# ui_ux6.net
KiCad netlist of a schematic drawn in Altium Designer
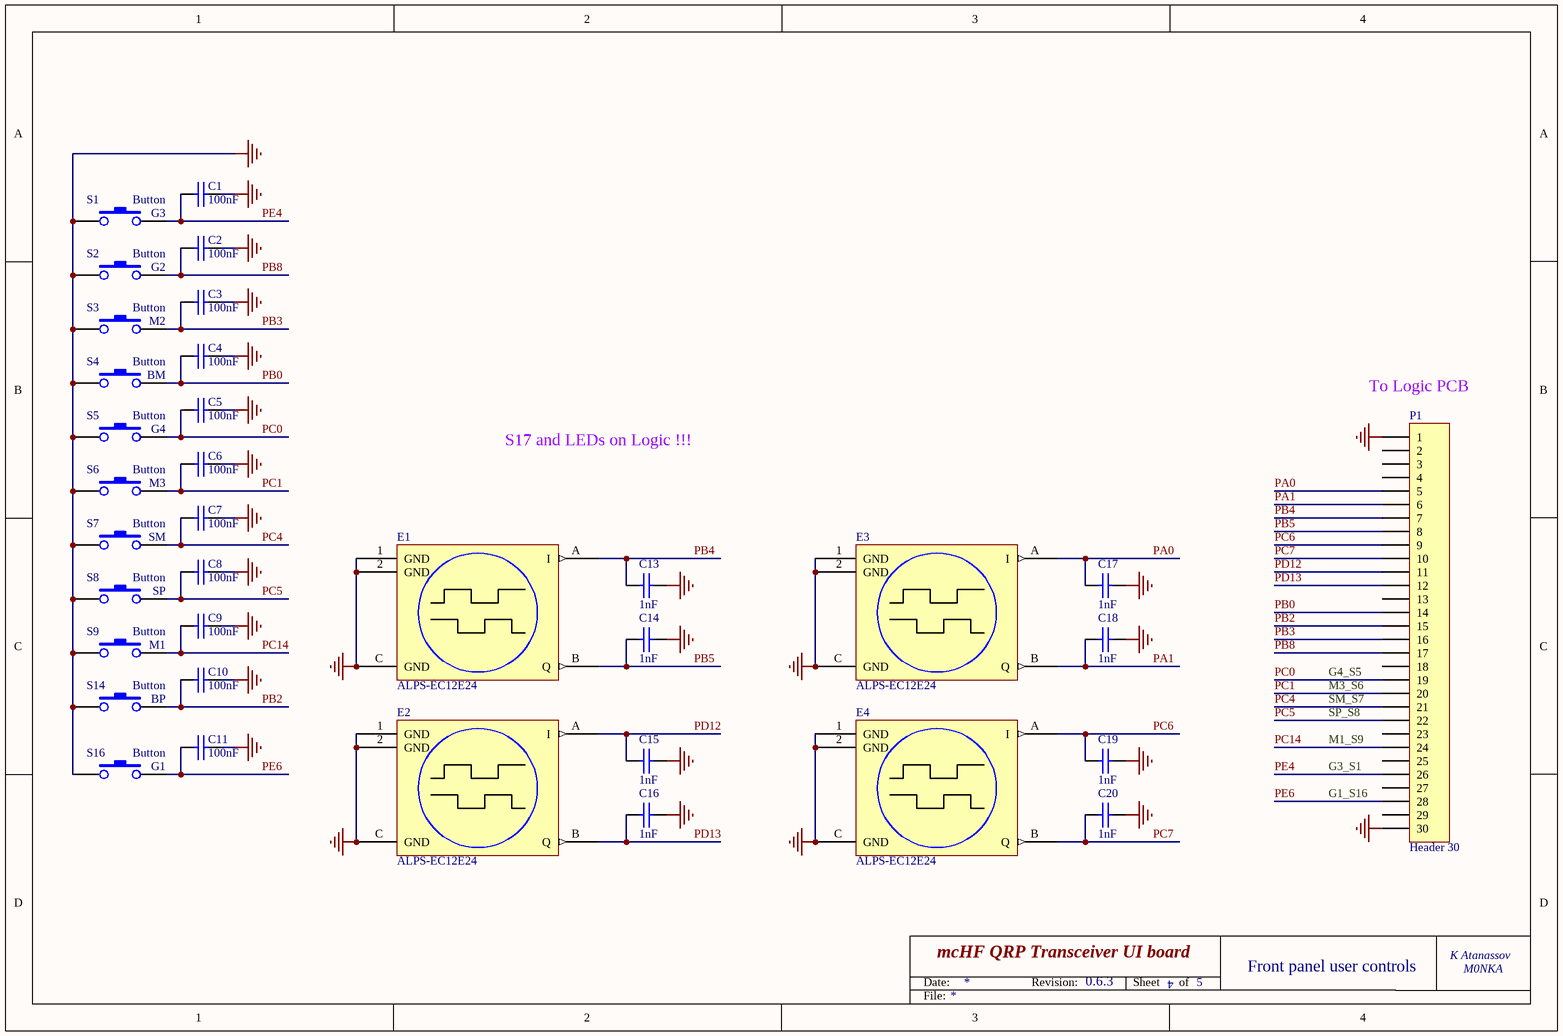
[diagram p0: ui_ux6.SchDoc]

(export (version "E")
  (design (tool "Eeschema 10.0.6"))
  (components
    (comp (ref "C1")
      (value "100nF")
      (footprint "0805-Pro")
      (description "Capacitor")
      (libsource (lib "mcHF_ui") (part "CAP"))
    )
    (comp (ref "C2")
      (value "100nF")
      (footprint "0805-Pro")
      (description "Capacitor")
      (libsource (lib "mcHF_ui") (part "CAP"))
    )
    (comp (ref "C3")
      (value "100nF")
      (footprint "0805-Pro")
      (description "Capacitor")
      (libsource (lib "mcHF_ui") (part "CAP"))
    )
    (comp (ref "C4")
      (value "100nF")
      (footprint "0805-Pro")
      (description "Capacitor")
      (libsource (lib "mcHF_ui") (part "CAP"))
    )
    (comp (ref "C5")
      (value "100nF")
      (footprint "0805-Pro")
      (description "Capacitor")
      (libsource (lib "mcHF_ui") (part "CAP"))
    )
    (comp (ref "C6")
      (value "100nF")
      (footprint "0805-Pro")
      (description "Capacitor")
      (libsource (lib "mcHF_ui") (part "CAP"))
    )
    (comp (ref "C7")
      (value "100nF")
      (footprint "0805-Pro")
      (description "Capacitor")
      (libsource (lib "mcHF_ui") (part "CAP"))
    )
    (comp (ref "C8")
      (value "100nF")
      (footprint "0805-Pro")
      (description "Capacitor")
      (libsource (lib "mcHF_ui") (part "CAP"))
    )
    (comp (ref "C9")
      (value "100nF")
      (footprint "0805-Pro")
      (description "Capacitor")
      (libsource (lib "mcHF_ui") (part "CAP"))
    )
    (comp (ref "C10")
      (value "100nF")
      (footprint "0805-Pro")
      (description "Capacitor")
      (libsource (lib "mcHF_ui") (part "CAP"))
    )
    (comp (ref "C11")
      (value "100nF")
      (footprint "0805-Pro")
      (description "Capacitor")
      (libsource (lib "mcHF_ui") (part "CAP"))
    )
    (comp (ref "C13")
      (value "1nF")
      (footprint "0805-Pro")
      (description "Capacitor")
      (libsource (lib "mcHF_ui") (part "CAP"))
    )
    (comp (ref "C14")
      (value "1nF")
      (footprint "0805-Pro")
      (description "Capacitor")
      (libsource (lib "mcHF_ui") (part "CAP"))
    )
    (comp (ref "C15")
      (value "1nF")
      (footprint "0805-Pro")
      (description "Capacitor")
      (libsource (lib "mcHF_ui") (part "CAP"))
    )
    (comp (ref "C16")
      (value "1nF")
      (footprint "0805-Pro")
      (description "Capacitor")
      (libsource (lib "mcHF_ui") (part "CAP"))
    )
    (comp (ref "C17")
      (value "1nF")
      (footprint "0805-Pro")
      (description "Capacitor")
      (libsource (lib "mcHF_ui") (part "CAP"))
    )
    (comp (ref "C18")
      (value "1nF")
      (footprint "0805-Pro")
      (description "Capacitor")
      (libsource (lib "mcHF_ui") (part "CAP"))
    )
    (comp (ref "C19")
      (value "1nF")
      (footprint "0805-Pro")
      (description "Capacitor")
      (libsource (lib "mcHF_ui") (part "CAP"))
    )
    (comp (ref "C20")
      (value "1nF")
      (footprint "0805-Pro")
      (description "Capacitor")
      (libsource (lib "mcHF_ui") (part "CAP"))
    )
    (comp (ref "E1")
      (value "ALPS-EC12E24")
      (footprint "Encoder")
      (description "ALPS Rotary Encoder")
      (libsource (lib "mcHF_ui") (part "Encoder"))
    )
    (comp (ref "E2")
      (value "ALPS-EC12E24")
      (footprint "Encoder")
      (description "ALPS Rotary Encoder")
      (libsource (lib "mcHF_ui") (part "Encoder"))
    )
    (comp (ref "E3")
      (value "ALPS-EC12E24")
      (footprint "Encoder")
      (description "ALPS Rotary Encoder")
      (libsource (lib "mcHF_ui") (part "Encoder"))
    )
    (comp (ref "E4")
      (value "ALPS-EC12E24")
      (footprint "Encoder")
      (description "ALPS Rotary Encoder")
      (libsource (lib "mcHF_ui") (part "Encoder"))
    )
    (comp (ref "P1")
      (value "Header 30")
      (footprint "HDR1X30")
      (description "Header, 30-Pin")
      (libsource (lib "mcHF_ui") (part "Header 30"))
    )
    (comp (ref "S1")
      (value "Button")
      (footprint "BUTTON_SMD2")
      (description "Push Button")
      (fields (field (name "SOFTWARE FUNCTION") "G3"))
      (libsource (lib "mcHF_ui") (part "SW-PB"))
    )
    (comp (ref "S2")
      (value "Button")
      (footprint "BUTTON_SMD2")
      (description "Push Button")
      (fields (field (name "SOFTWARE FUNCTION") "G2"))
      (libsource (lib "mcHF_ui") (part "SW-PB"))
    )
    (comp (ref "S3")
      (value "Button")
      (footprint "BUTTON_SMD2")
      (description "Push Button")
      (fields (field (name "SOFTWARE FUNCTION") "M2"))
      (libsource (lib "mcHF_ui") (part "SW-PB"))
    )
    (comp (ref "S4")
      (value "Button")
      (footprint "BUTTON_SMD2")
      (description "Push Button")
      (fields (field (name "SOFTWARE FUNCTION") "BM"))
      (libsource (lib "mcHF_ui") (part "SW-PB"))
    )
    (comp (ref "S5")
      (value "Button")
      (footprint "BUTTON_SMD2")
      (description "Push Button")
      (fields (field (name "SOFTWARE FUNCTION") "G4"))
      (libsource (lib "mcHF_ui") (part "SW-PB"))
    )
    (comp (ref "S6")
      (value "Button")
      (footprint "BUTTON_SMD2")
      (description "Push Button")
      (fields (field (name "SOFTWARE FUNCTION") "M3"))
      (libsource (lib "mcHF_ui") (part "SW-PB"))
    )
    (comp (ref "S7")
      (value "Button")
      (footprint "BUTTON_SMD2")
      (description "Push Button")
      (fields (field (name "SOFTWARE FUNCTION") "SM"))
      (libsource (lib "mcHF_ui") (part "SW-PB"))
    )
    (comp (ref "S8")
      (value "Button")
      (footprint "BUTTON_SMD2")
      (description "Push Button")
      (fields (field (name "SOFTWARE FUNCTION") "SP"))
      (libsource (lib "mcHF_ui") (part "SW-PB"))
    )
    (comp (ref "S9")
      (value "Button")
      (footprint "BUTTON_SMD2")
      (description "Push Button")
      (fields (field (name "SOFTWARE FUNCTION") "M1"))
      (libsource (lib "mcHF_ui") (part "SW-PB"))
    )
    (comp (ref "S14")
      (value "Button")
      (footprint "BUTTON_SMD2")
      (description "Push Button")
      (fields (field (name "SOFTWARE FUNCTION") "BP"))
      (libsource (lib "mcHF_ui") (part "SW-PB"))
    )
    (comp (ref "S16")
      (value "Button")
      (footprint "BUTTON_SMD2")
      (description "Push Button")
      (fields (field (name "SOFTWARE FUNCTION") "G1"))
      (libsource (lib "mcHF_ui") (part "SW-PB"))
    )
  )
  (nets
    (net (code "1") (name "/PA0") (class "Default")
      (node (ref "C17") (pin "1") (pinfunction "1_1") (pintype "passive"))
      (node (ref "E3") (pin "A") (pinfunction "I_A") (pintype "output"))
      (node (ref "P1") (pin "5") (pinfunction "5_5") (pintype "passive"))
    )
    (net (code "2") (name "/PA1") (class "Default")
      (node (ref "C18") (pin "1") (pinfunction "1_1") (pintype "passive"))
      (node (ref "E3") (pin "B") (pinfunction "Q_B") (pintype "output"))
      (node (ref "P1") (pin "6") (pinfunction "6_6") (pintype "passive"))
    )
    (net (code "3") (name "/PB0") (class "Default")
      (node (ref "C4") (pin "2") (pinfunction "2_2") (pintype "passive"))
      (node (ref "P1") (pin "14") (pinfunction "14_14") (pintype "passive"))
      (node (ref "S4") (pin "2") (pinfunction "2_2") (pintype "passive"))
    )
    (net (code "4") (name "/PB2") (class "Default")
      (node (ref "C10") (pin "2") (pinfunction "2_2") (pintype "passive"))
      (node (ref "P1") (pin "15") (pinfunction "15_15") (pintype "passive"))
      (node (ref "S14") (pin "2") (pinfunction "2_2") (pintype "passive"))
    )
    (net (code "5") (name "/PB3") (class "Default")
      (node (ref "C3") (pin "2") (pinfunction "2_2") (pintype "passive"))
      (node (ref "P1") (pin "16") (pinfunction "16_16") (pintype "passive"))
      (node (ref "S3") (pin "2") (pinfunction "2_2") (pintype "passive"))
    )
    (net (code "6") (name "/PB4") (class "Default")
      (node (ref "C13") (pin "1") (pinfunction "1_1") (pintype "passive"))
      (node (ref "E1") (pin "A") (pinfunction "I_A") (pintype "output"))
      (node (ref "P1") (pin "7") (pinfunction "7_7") (pintype "passive"))
    )
    (net (code "7") (name "/PB5") (class "Default")
      (node (ref "C14") (pin "1") (pinfunction "1_1") (pintype "passive"))
      (node (ref "E1") (pin "B") (pinfunction "Q_B") (pintype "output"))
      (node (ref "P1") (pin "8") (pinfunction "8_8") (pintype "passive"))
    )
    (net (code "8") (name "/PB8") (class "Default")
      (node (ref "C2") (pin "2") (pinfunction "2_2") (pintype "passive"))
      (node (ref "P1") (pin "17") (pinfunction "17_17") (pintype "passive"))
      (node (ref "S2") (pin "2") (pinfunction "2_2") (pintype "passive"))
    )
    (net (code "9") (name "/PC0") (class "Default")
      (node (ref "C5") (pin "2") (pinfunction "2_2") (pintype "passive"))
      (node (ref "P1") (pin "19") (pinfunction "19_19") (pintype "passive"))
      (node (ref "S5") (pin "2") (pinfunction "2_2") (pintype "passive"))
    )
    (net (code "10") (name "/PC1") (class "Default")
      (node (ref "C6") (pin "2") (pinfunction "2_2") (pintype "passive"))
      (node (ref "P1") (pin "20") (pinfunction "20_20") (pintype "passive"))
      (node (ref "S6") (pin "2") (pinfunction "2_2") (pintype "passive"))
    )
    (net (code "11") (name "/PC4") (class "Default")
      (node (ref "C7") (pin "2") (pinfunction "2_2") (pintype "passive"))
      (node (ref "P1") (pin "21") (pinfunction "21_21") (pintype "passive"))
      (node (ref "S7") (pin "2") (pinfunction "2_2") (pintype "passive"))
    )
    (net (code "12") (name "/PC5") (class "Default")
      (node (ref "C8") (pin "2") (pinfunction "2_2") (pintype "passive"))
      (node (ref "P1") (pin "22") (pinfunction "22_22") (pintype "passive"))
      (node (ref "S8") (pin "2") (pinfunction "2_2") (pintype "passive"))
    )
    (net (code "13") (name "/PC6") (class "Default")
      (node (ref "C19") (pin "1") (pinfunction "1_1") (pintype "passive"))
      (node (ref "E4") (pin "A") (pinfunction "I_A") (pintype "output"))
      (node (ref "P1") (pin "9") (pinfunction "9_9") (pintype "passive"))
    )
    (net (code "14") (name "/PC7") (class "Default")
      (node (ref "C20") (pin "1") (pinfunction "1_1") (pintype "passive"))
      (node (ref "E4") (pin "B") (pinfunction "Q_B") (pintype "output"))
      (node (ref "P1") (pin "10") (pinfunction "10_10") (pintype "passive"))
    )
    (net (code "15") (name "/PC14") (class "Default")
      (node (ref "C9") (pin "2") (pinfunction "2_2") (pintype "passive"))
      (node (ref "P1") (pin "24") (pinfunction "24_24") (pintype "passive"))
      (node (ref "S9") (pin "2") (pinfunction "2_2") (pintype "passive"))
    )
    (net (code "16") (name "/PD12") (class "Default")
      (node (ref "C15") (pin "1") (pinfunction "1_1") (pintype "passive"))
      (node (ref "E2") (pin "A") (pinfunction "I_A") (pintype "output"))
      (node (ref "P1") (pin "11") (pinfunction "11_11") (pintype "passive"))
    )
    (net (code "17") (name "/PD13") (class "Default")
      (node (ref "C16") (pin "1") (pinfunction "1_1") (pintype "passive"))
      (node (ref "E2") (pin "B") (pinfunction "Q_B") (pintype "output"))
      (node (ref "P1") (pin "12") (pinfunction "12_12") (pintype "passive"))
    )
    (net (code "18") (name "/PE4") (class "Default")
      (node (ref "C1") (pin "2") (pinfunction "2_2") (pintype "passive"))
      (node (ref "P1") (pin "26") (pinfunction "26_26") (pintype "passive"))
      (node (ref "S1") (pin "2") (pinfunction "2_2") (pintype "passive"))
    )
    (net (code "19") (name "/PE6") (class "Default")
      (node (ref "C11") (pin "2") (pinfunction "2_2") (pintype "passive"))
      (node (ref "P1") (pin "28") (pinfunction "28_28") (pintype "passive"))
      (node (ref "S16") (pin "2") (pinfunction "2_2") (pintype "passive"))
    )
    (net (code "20") (name "GND") (class "Default")
      (node (ref "C1") (pin "1") (pinfunction "1_1") (pintype "passive"))
      (node (ref "C10") (pin "1") (pinfunction "1_1") (pintype "passive"))
      (node (ref "C11") (pin "1") (pinfunction "1_1") (pintype "passive"))
      (node (ref "C13") (pin "2") (pinfunction "2_2") (pintype "passive"))
      (node (ref "C14") (pin "2") (pinfunction "2_2") (pintype "passive"))
      (node (ref "C15") (pin "2") (pinfunction "2_2") (pintype "passive"))
      (node (ref "C16") (pin "2") (pinfunction "2_2") (pintype "passive"))
      (node (ref "C17") (pin "2") (pinfunction "2_2") (pintype "passive"))
      (node (ref "C18") (pin "2") (pinfunction "2_2") (pintype "passive"))
      (node (ref "C19") (pin "2") (pinfunction "2_2") (pintype "passive"))
      (node (ref "C2") (pin "1") (pinfunction "1_1") (pintype "passive"))
      (node (ref "C20") (pin "2") (pinfunction "2_2") (pintype "passive"))
      (node (ref "C3") (pin "1") (pinfunction "1_1") (pintype "passive"))
      (node (ref "C4") (pin "1") (pinfunction "1_1") (pintype "passive"))
      (node (ref "C5") (pin "1") (pinfunction "1_1") (pintype "passive"))
      (node (ref "C6") (pin "1") (pinfunction "1_1") (pintype "passive"))
      (node (ref "C7") (pin "1") (pinfunction "1_1") (pintype "passive"))
      (node (ref "C8") (pin "1") (pinfunction "1_1") (pintype "passive"))
      (node (ref "C9") (pin "1") (pinfunction "1_1") (pintype "passive"))
      (node (ref "E1") (pin "1") (pinfunction "GND_1") (pintype "power_in"))
      (node (ref "E1") (pin "2") (pinfunction "GND_2") (pintype "power_in"))
      (node (ref "E1") (pin "C") (pinfunction "GND_C") (pintype "power_in"))
      (node (ref "E2") (pin "1") (pinfunction "GND_1") (pintype "power_in"))
      (node (ref "E2") (pin "2") (pinfunction "GND_2") (pintype "power_in"))
      (node (ref "E2") (pin "C") (pinfunction "GND_C") (pintype "power_in"))
      (node (ref "E3") (pin "1") (pinfunction "GND_1") (pintype "power_in"))
      (node (ref "E3") (pin "2") (pinfunction "GND_2") (pintype "power_in"))
      (node (ref "E3") (pin "C") (pinfunction "GND_C") (pintype "power_in"))
      (node (ref "E4") (pin "1") (pinfunction "GND_1") (pintype "power_in"))
      (node (ref "E4") (pin "2") (pinfunction "GND_2") (pintype "power_in"))
      (node (ref "E4") (pin "C") (pinfunction "GND_C") (pintype "power_in"))
      (node (ref "P1") (pin "1") (pinfunction "1_1") (pintype "passive"))
      (node (ref "P1") (pin "30") (pinfunction "30_30") (pintype "passive"))
      (node (ref "S1") (pin "1") (pinfunction "1_1") (pintype "passive"))
      (node (ref "S14") (pin "1") (pinfunction "1_1") (pintype "passive"))
      (node (ref "S16") (pin "1") (pinfunction "1_1") (pintype "passive"))
      (node (ref "S2") (pin "1") (pinfunction "1_1") (pintype "passive"))
      (node (ref "S3") (pin "1") (pinfunction "1_1") (pintype "passive"))
      (node (ref "S4") (pin "1") (pinfunction "1_1") (pintype "passive"))
      (node (ref "S5") (pin "1") (pinfunction "1_1") (pintype "passive"))
      (node (ref "S6") (pin "1") (pinfunction "1_1") (pintype "passive"))
      (node (ref "S7") (pin "1") (pinfunction "1_1") (pintype "passive"))
      (node (ref "S8") (pin "1") (pinfunction "1_1") (pintype "passive"))
      (node (ref "S9") (pin "1") (pinfunction "1_1") (pintype "passive"))
    )
    (net (code "21") (name "unconnected-(P1-Pad2)") (class "Default")
      (node (ref "P1") (pin "2") (pinfunction "2_2") (pintype "passive"))
    )
    (net (code "22") (name "unconnected-(P1-Pad3)") (class "Default")
      (node (ref "P1") (pin "3") (pinfunction "3_3") (pintype "passive"))
    )
    (net (code "23") (name "unconnected-(P1-Pad4)") (class "Default")
      (node (ref "P1") (pin "4") (pinfunction "4_4") (pintype "passive"))
    )
    (net (code "24") (name "unconnected-(P1-Pad13)") (class "Default")
      (node (ref "P1") (pin "13") (pinfunction "13_13") (pintype "passive"))
    )
    (net (code "25") (name "unconnected-(P1-Pad18)") (class "Default")
      (node (ref "P1") (pin "18") (pinfunction "18_18") (pintype "passive"))
    )
    (net (code "26") (name "unconnected-(P1-Pad23)") (class "Default")
      (node (ref "P1") (pin "23") (pinfunction "23_23") (pintype "passive"))
    )
    (net (code "27") (name "unconnected-(P1-Pad25)") (class "Default")
      (node (ref "P1") (pin "25") (pinfunction "25_25") (pintype "passive"))
    )
    (net (code "28") (name "unconnected-(P1-Pad27)") (class "Default")
      (node (ref "P1") (pin "27") (pinfunction "27_27") (pintype "passive"))
    )
    (net (code "29") (name "unconnected-(P1-Pad29)") (class "Default")
      (node (ref "P1") (pin "29") (pinfunction "29_29") (pintype "passive"))
    )
  )
)
